# Spectra_Mirror_Bottom_Board_Final.net
KiCad netlist of a schematic drawn in EAGLE
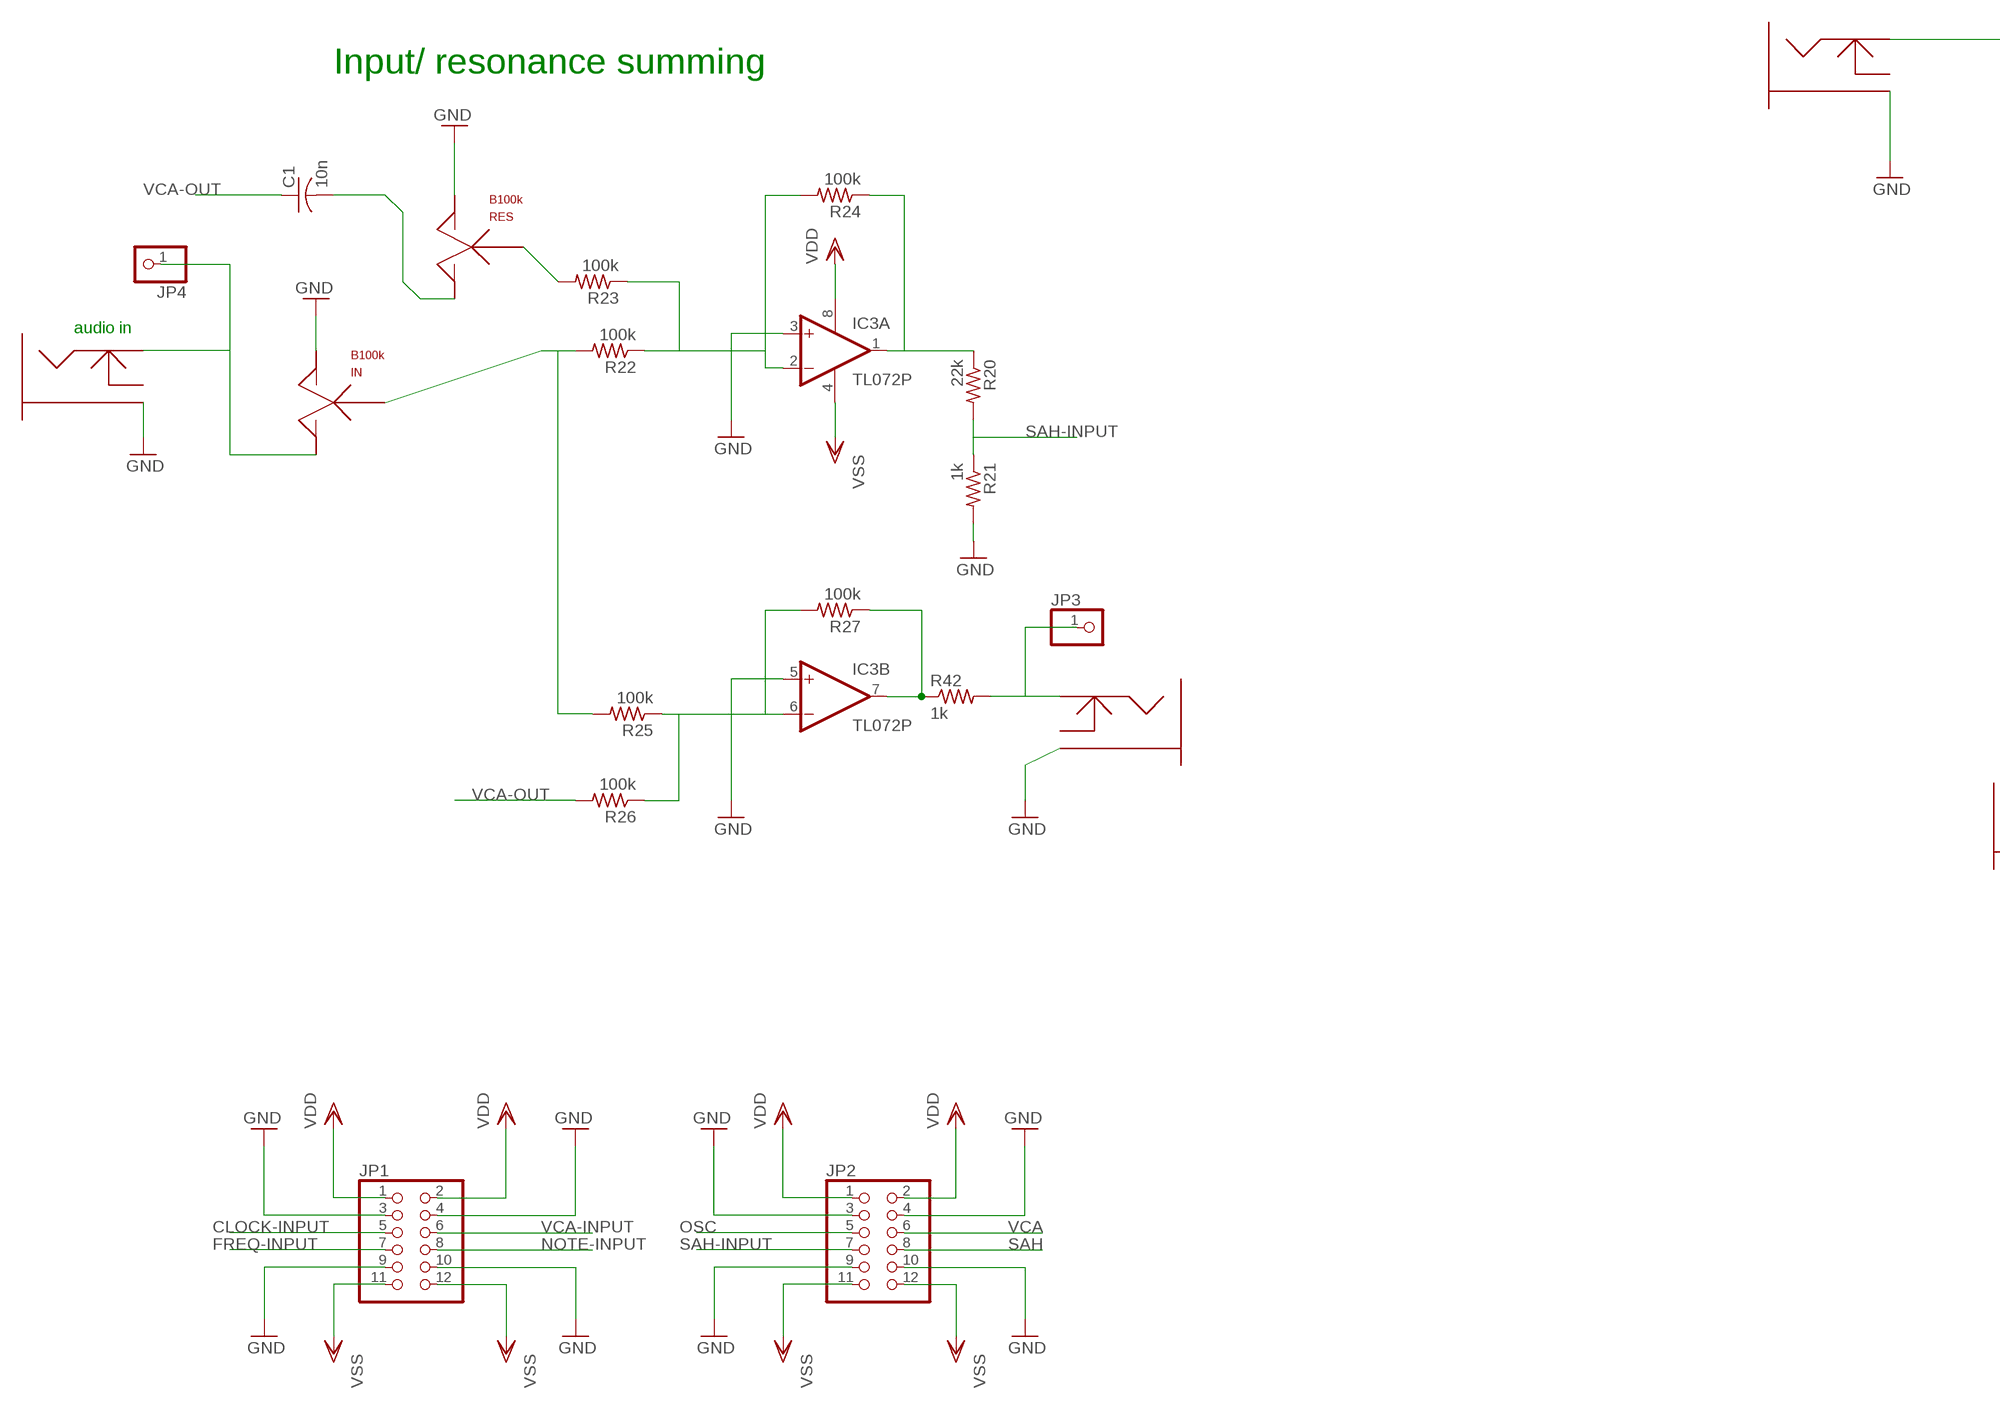
[diagram p0: schematic, sheet 1, part 1 of 2]
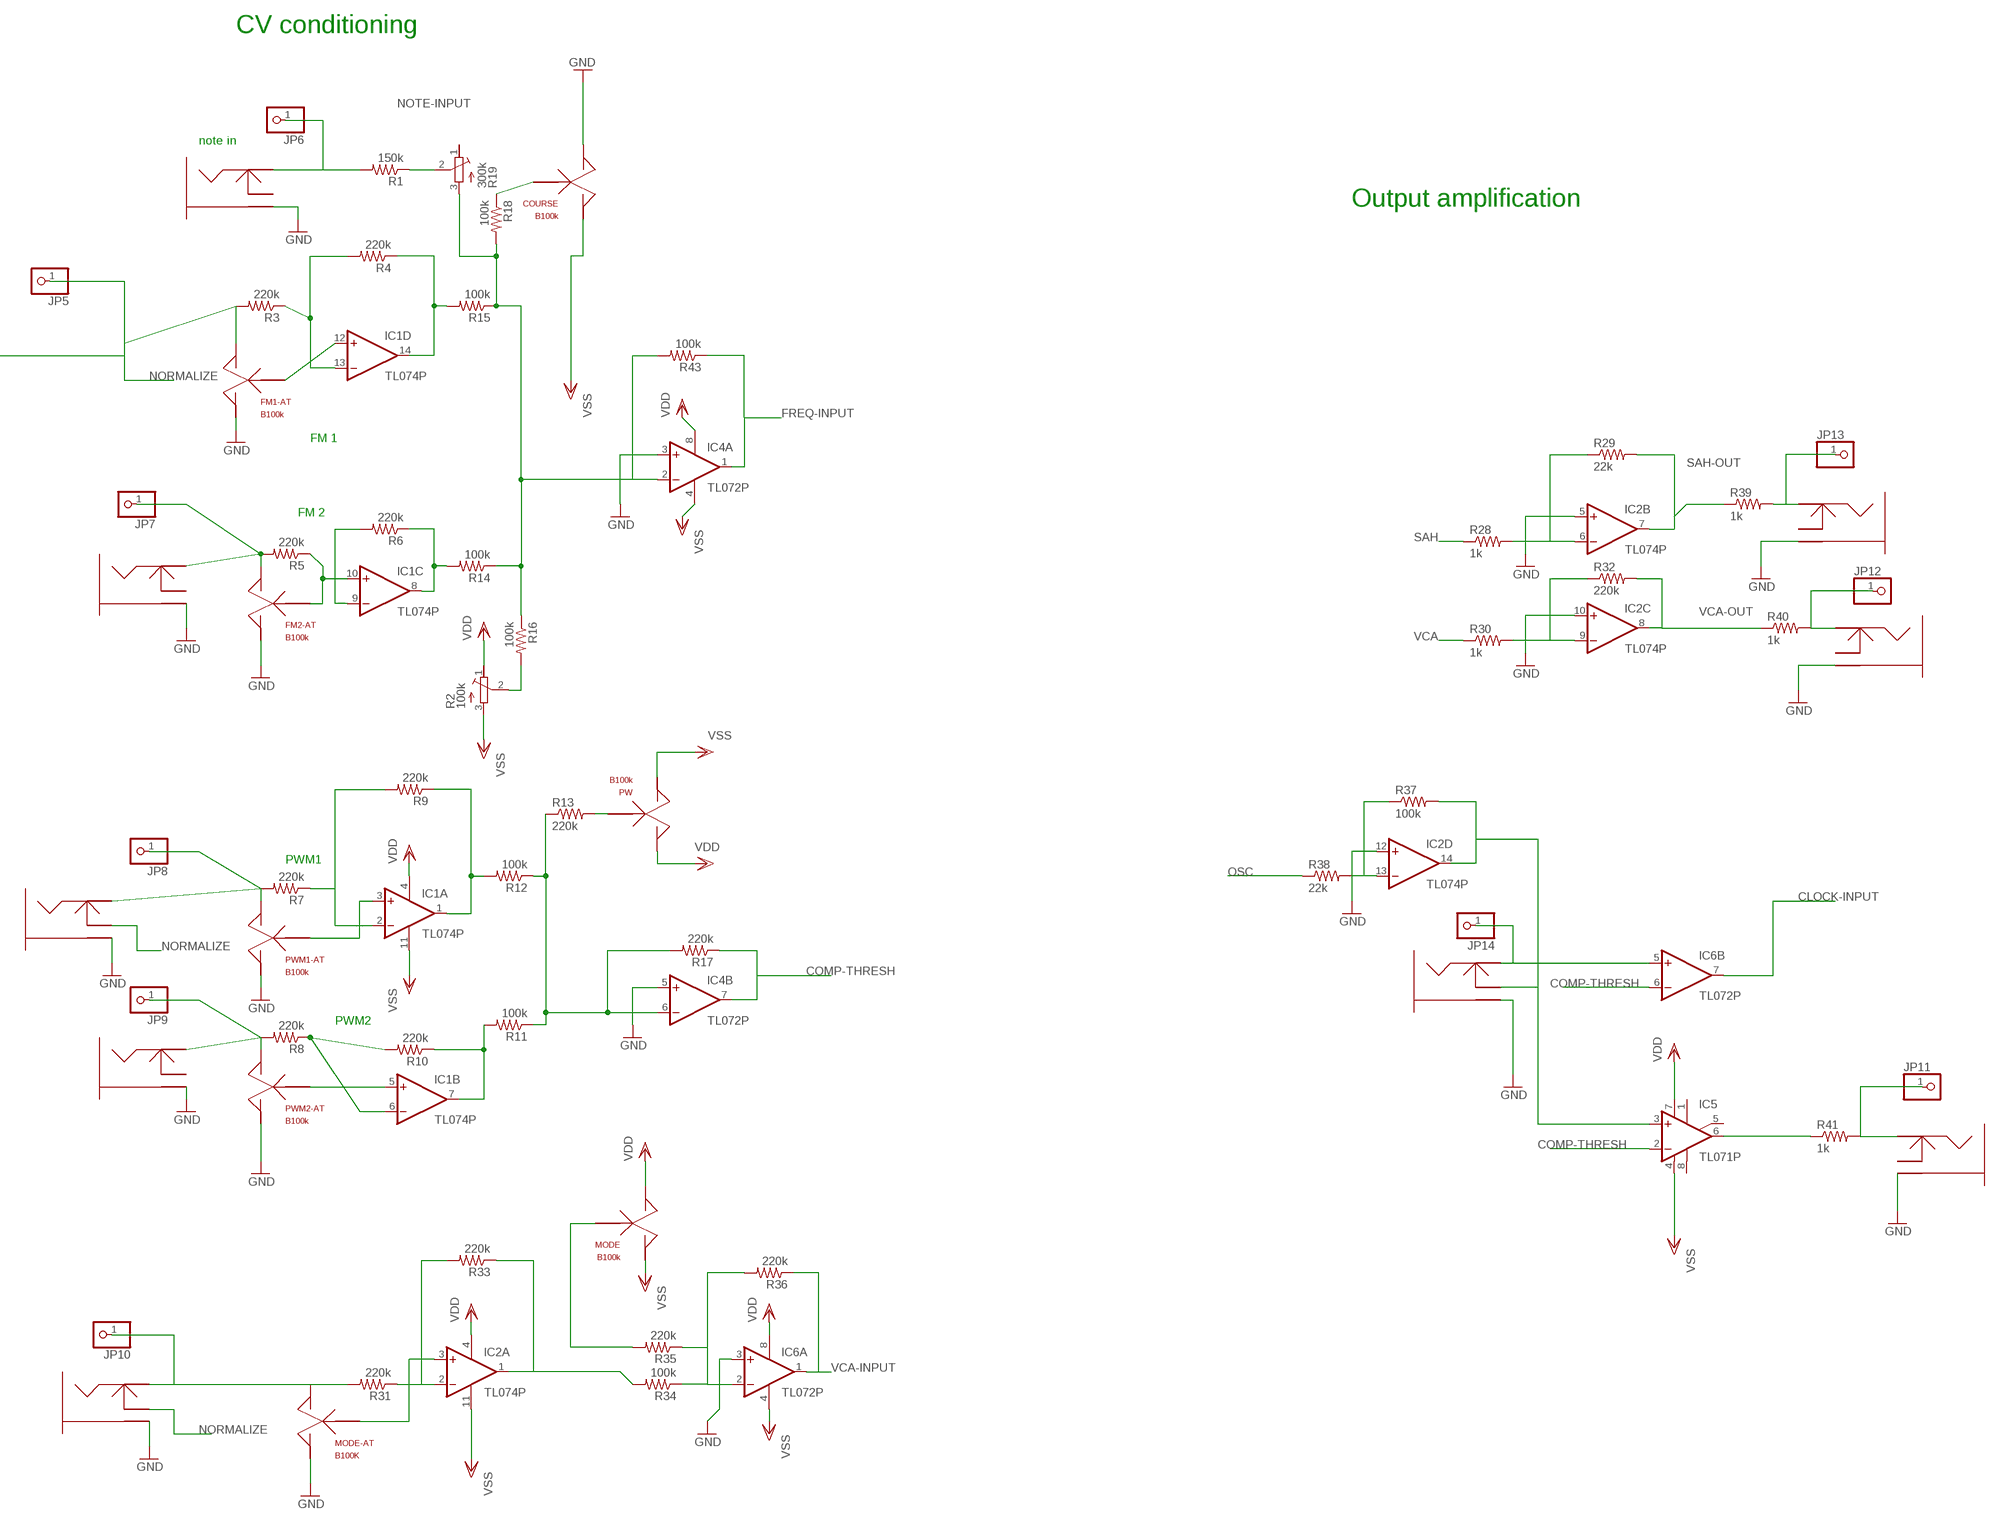
[diagram p1: schematic, sheet 1, part 2 of 2]

(export (version "E")
  (design (tool "Eeschema 10.0.6"))
  (components
    (comp (ref "C1")
      (value "10n")
      (footprint "eagle-import:C050-025X075")
      (libsource (lib "eagle-import") (part "C-US050-025X075"))
    )
    (comp (ref "COURSE")
      (value "B100k")
      (footprint "eagle-import:ALPHAPOT_BOARDMOUNT")
      (libsource (lib "eagle-import") (part "ALPHAPOT_BOARDMOUNT"))
    )
    (comp (ref "FM1-AT")
      (value "B100k")
      (footprint "eagle-import:ALPHAPOT_BOARDMOUNT")
      (libsource (lib "eagle-import") (part "ALPHAPOT_BOARDMOUNT"))
    )
    (comp (ref "FM2-AT")
      (value "B100k")
      (footprint "eagle-import:ALPHAPOT_BOARDMOUNT")
      (libsource (lib "eagle-import") (part "ALPHAPOT_BOARDMOUNT"))
    )
    (comp (ref "IC1")
      (value "TL074P")
      (footprint "eagle-import:DIL14")
      (libsource (lib "eagle-import") (part "TL074P"))
    )
    (comp (ref "IC2")
      (value "TL074P")
      (footprint "eagle-import:DIL14")
      (libsource (lib "eagle-import") (part "TL074P"))
    )
    (comp (ref "IC3")
      (value "TL072P")
      (footprint "eagle-import:DIL08")
      (libsource (lib "eagle-import") (part "TL072P"))
    )
    (comp (ref "IC4")
      (value "TL072P")
      (footprint "eagle-import:DIL08")
      (libsource (lib "eagle-import") (part "TL072P"))
    )
    (comp (ref "IC5")
      (value "TL071P")
      (footprint "eagle-import:DIL08")
      (libsource (lib "eagle-import") (part "TL071P"))
    )
    (comp (ref "IC6")
      (value "TL072P")
      (footprint "eagle-import:DIL08")
      (libsource (lib "eagle-import") (part "TL072P"))
    )
    (comp (ref "IN")
      (value "B100k")
      (footprint "eagle-import:ALPHAPOT_BOARDMOUNT")
      (libsource (lib "eagle-import") (part "ALPHAPOT_BOARDMOUNT"))
    )
    (comp (ref "JP1")
      (value "PINHD-2X6")
      (footprint "eagle-import:2X06")
      (libsource (lib "eagle-import") (part "PINHD-2X6"))
    )
    (comp (ref "JP2")
      (value "PINHD-2X6")
      (footprint "eagle-import:2X06")
      (libsource (lib "eagle-import") (part "PINHD-2X6"))
    )
    (comp (ref "JP3")
      (value "PINHD-1X1")
      (footprint "eagle-import:1X01")
      (libsource (lib "eagle-import") (part "PINHD-1X1"))
    )
    (comp (ref "JP4")
      (value "PINHD-1X1")
      (footprint "eagle-import:1X01")
      (libsource (lib "eagle-import") (part "PINHD-1X1"))
    )
    (comp (ref "JP5")
      (value "PINHD-1X1")
      (footprint "eagle-import:1X01")
      (libsource (lib "eagle-import") (part "PINHD-1X1"))
    )
    (comp (ref "JP6")
      (value "PINHD-1X1")
      (footprint "eagle-import:1X01")
      (libsource (lib "eagle-import") (part "PINHD-1X1"))
    )
    (comp (ref "JP7")
      (value "PINHD-1X1")
      (footprint "eagle-import:1X01")
      (libsource (lib "eagle-import") (part "PINHD-1X1"))
    )
    (comp (ref "JP8")
      (value "PINHD-1X1")
      (footprint "eagle-import:1X01")
      (libsource (lib "eagle-import") (part "PINHD-1X1"))
    )
    (comp (ref "JP9")
      (value "PINHD-1X1")
      (footprint "eagle-import:1X01")
      (libsource (lib "eagle-import") (part "PINHD-1X1"))
    )
    (comp (ref "JP10")
      (value "PINHD-1X1")
      (footprint "eagle-import:1X01")
      (libsource (lib "eagle-import") (part "PINHD-1X1"))
    )
    (comp (ref "JP11")
      (value "PINHD-1X1")
      (footprint "eagle-import:1X01")
      (libsource (lib "eagle-import") (part "PINHD-1X1"))
    )
    (comp (ref "JP12")
      (value "PINHD-1X1")
      (footprint "eagle-import:1X01")
      (libsource (lib "eagle-import") (part "PINHD-1X1"))
    )
    (comp (ref "JP13")
      (value "PINHD-1X1")
      (footprint "eagle-import:1X01")
      (libsource (lib "eagle-import") (part "PINHD-1X1"))
    )
    (comp (ref "JP14")
      (value "PINHD-1X1")
      (footprint "eagle-import:1X01")
      (libsource (lib "eagle-import") (part "PINHD-1X1"))
    )
    (comp (ref "MODE")
      (value "B100k")
      (footprint "eagle-import:ALPHAPOT_BOARDMOUNT")
      (libsource (lib "eagle-import") (part "ALPHAPOT_BOARDMOUNT"))
    )
    (comp (ref "MODE-AT")
      (value "B100K")
      (footprint "eagle-import:ALPHAPOT_BOARDMOUNT")
      (libsource (lib "eagle-import") (part "ALPHAPOT_BOARDMOUNT"))
    )
    (comp (ref "PW")
      (value "B100k")
      (footprint "eagle-import:ALPHAPOT_BOARDMOUNT")
      (libsource (lib "eagle-import") (part "ALPHAPOT_BOARDMOUNT"))
    )
    (comp (ref "PWM1-AT")
      (value "B100k")
      (footprint "eagle-import:ALPHAPOT_BOARDMOUNT")
      (libsource (lib "eagle-import") (part "ALPHAPOT_BOARDMOUNT"))
    )
    (comp (ref "PWM2-AT")
      (value "B100k")
      (footprint "eagle-import:ALPHAPOT_BOARDMOUNT")
      (libsource (lib "eagle-import") (part "ALPHAPOT_BOARDMOUNT"))
    )
    (comp (ref "R1")
      (value "150k")
      (footprint "eagle-import:0204_7")
      (libsource (lib "eagle-import") (part "R-US_0204/7"))
    )
    (comp (ref "R2")
      (value "100k")
      (footprint "eagle-import:RTRIMT93YA")
      (libsource (lib "eagle-import") (part "R-TRIMMT93YA"))
    )
    (comp (ref "R3")
      (value "220k")
      (footprint "eagle-import:0204_7")
      (libsource (lib "eagle-import") (part "R-US_0204/7"))
    )
    (comp (ref "R4")
      (value "220k")
      (footprint "eagle-import:0204V")
      (libsource (lib "eagle-import") (part "R-US_0204/2V"))
    )
    (comp (ref "R5")
      (value "220k")
      (footprint "eagle-import:0204_7")
      (libsource (lib "eagle-import") (part "R-US_0204/7"))
    )
    (comp (ref "R6")
      (value "220k")
      (footprint "eagle-import:0204V")
      (libsource (lib "eagle-import") (part "R-US_0204/2V"))
    )
    (comp (ref "R7")
      (value "220k")
      (footprint "eagle-import:0204_7")
      (libsource (lib "eagle-import") (part "R-US_0204/7"))
    )
    (comp (ref "R8")
      (value "220k")
      (footprint "eagle-import:0204_7")
      (libsource (lib "eagle-import") (part "R-US_0204/7"))
    )
    (comp (ref "R9")
      (value "220k")
      (footprint "eagle-import:0204V")
      (libsource (lib "eagle-import") (part "R-US_0204/2V"))
    )
    (comp (ref "R10")
      (value "220k")
      (footprint "eagle-import:0204_7")
      (libsource (lib "eagle-import") (part "R-US_0204/7"))
    )
    (comp (ref "R11")
      (value "100k")
      (footprint "eagle-import:0204_7")
      (libsource (lib "eagle-import") (part "R-US_0204/7"))
    )
    (comp (ref "R12")
      (value "100k")
      (footprint "eagle-import:0204_7")
      (libsource (lib "eagle-import") (part "R-US_0204/7"))
    )
    (comp (ref "R13")
      (value "220k")
      (footprint "eagle-import:0204_7")
      (libsource (lib "eagle-import") (part "R-US_0204/7"))
    )
    (comp (ref "R14")
      (value "100k")
      (footprint "eagle-import:0204_7")
      (libsource (lib "eagle-import") (part "R-US_0204/7"))
    )
    (comp (ref "R15")
      (value "100k")
      (footprint "eagle-import:0204_7")
      (libsource (lib "eagle-import") (part "R-US_0204/7"))
    )
    (comp (ref "R16")
      (value "100k")
      (footprint "eagle-import:0204_7")
      (libsource (lib "eagle-import") (part "R-US_0204/7"))
    )
    (comp (ref "R17")
      (value "220k")
      (footprint "eagle-import:0204_7")
      (libsource (lib "eagle-import") (part "R-US_0204/7"))
    )
    (comp (ref "R18")
      (value "100k")
      (footprint "eagle-import:0204_7")
      (libsource (lib "eagle-import") (part "R-US_0204/7"))
    )
    (comp (ref "R19")
      (value "300k")
      (footprint "eagle-import:RTRIMT93YA")
      (libsource (lib "eagle-import") (part "R-TRIMMT93YA"))
    )
    (comp (ref "R20")
      (value "22k")
      (footprint "eagle-import:0204_7")
      (libsource (lib "eagle-import") (part "R-US_0204/7"))
    )
    (comp (ref "R21")
      (value "1k")
      (footprint "eagle-import:0204_7")
      (libsource (lib "eagle-import") (part "R-US_0204/7"))
    )
    (comp (ref "R22")
      (value "100k")
      (footprint "eagle-import:0204_7")
      (libsource (lib "eagle-import") (part "R-US_0204/7"))
    )
    (comp (ref "R23")
      (value "100k")
      (footprint "eagle-import:0204_7")
      (libsource (lib "eagle-import") (part "R-US_0204/7"))
    )
    (comp (ref "R24")
      (value "100k")
      (footprint "eagle-import:0204_7")
      (libsource (lib "eagle-import") (part "R-US_0204/7"))
    )
    (comp (ref "R25")
      (value "100k")
      (footprint "eagle-import:0204_7")
      (libsource (lib "eagle-import") (part "R-US_0204/7"))
    )
    (comp (ref "R26")
      (value "100k")
      (footprint "eagle-import:0204_7")
      (libsource (lib "eagle-import") (part "R-US_0204/7"))
    )
    (comp (ref "R27")
      (value "100k")
      (footprint "eagle-import:0204_7")
      (libsource (lib "eagle-import") (part "R-US_0204/7"))
    )
    (comp (ref "R28")
      (value "1k")
      (footprint "eagle-import:0204_7")
      (libsource (lib "eagle-import") (part "R-US_0204/7"))
    )
    (comp (ref "R29")
      (value "22k")
      (footprint "eagle-import:0204V")
      (libsource (lib "eagle-import") (part "R-US_0204/2V"))
    )
    (comp (ref "R30")
      (value "1k")
      (footprint "eagle-import:0204_7")
      (libsource (lib "eagle-import") (part "R-US_0204/7"))
    )
    (comp (ref "R31")
      (value "220k")
      (footprint "eagle-import:0204_7")
      (libsource (lib "eagle-import") (part "R-US_0204/7"))
    )
    (comp (ref "R32")
      (value "220k")
      (footprint "eagle-import:0204_7")
      (libsource (lib "eagle-import") (part "R-US_0204/7"))
    )
    (comp (ref "R33")
      (value "220k")
      (footprint "eagle-import:0204V")
      (libsource (lib "eagle-import") (part "R-US_0204/2V"))
    )
    (comp (ref "R34")
      (value "100k")
      (footprint "eagle-import:0204_7")
      (libsource (lib "eagle-import") (part "R-US_0204/7"))
    )
    (comp (ref "R35")
      (value "220k")
      (footprint "eagle-import:0204_7")
      (libsource (lib "eagle-import") (part "R-US_0204/7"))
    )
    (comp (ref "R36")
      (value "220k")
      (footprint "eagle-import:0204_7")
      (libsource (lib "eagle-import") (part "R-US_0204/7"))
    )
    (comp (ref "R37")
      (value "100k")
      (footprint "eagle-import:0204V")
      (libsource (lib "eagle-import") (part "R-US_0204/2V"))
    )
    (comp (ref "R38")
      (value "22k")
      (footprint "eagle-import:0204_7")
      (libsource (lib "eagle-import") (part "R-US_0204/7"))
    )
    (comp (ref "R39")
      (value "1k")
      (footprint "eagle-import:0204_7")
      (libsource (lib "eagle-import") (part "R-US_0204/7"))
    )
    (comp (ref "R40")
      (value "1k")
      (footprint "eagle-import:0204_7")
      (libsource (lib "eagle-import") (part "R-US_0204/7"))
    )
    (comp (ref "R41")
      (value "1k")
      (footprint "eagle-import:0204_7")
      (libsource (lib "eagle-import") (part "R-US_0204/7"))
    )
    (comp (ref "R42")
      (value "1k")
      (footprint "eagle-import:0204_7")
      (libsource (lib "eagle-import") (part "R-US_0204/7"))
    )
    (comp (ref "R43")
      (value "100k")
      (footprint "eagle-import:0204_7")
      (libsource (lib "eagle-import") (part "R-US_0204/7"))
    )
    (comp (ref "RES")
      (value "B100k")
      (footprint "eagle-import:ALPHAPOT_BOARDMOUNT")
      (libsource (lib "eagle-import") (part "ALPHAPOT_BOARDMOUNT"))
    )
    (comp (ref "U$1")
      (value "KOBICONPJ-301")
      (footprint "eagle-import:KOBICONPJ-301")
      (libsource (lib "eagle-import") (part "KOBICONPJ-301"))
    )
    (comp (ref "U$2")
      (value "KOBICONPJ-301")
      (footprint "eagle-import:KOBICONPJ-301")
      (libsource (lib "eagle-import") (part "KOBICONPJ-301"))
    )
    (comp (ref "U$3")
      (value "KOBICONPJ-301")
      (footprint "eagle-import:KOBICONPJ-301")
      (libsource (lib "eagle-import") (part "KOBICONPJ-301"))
    )
    (comp (ref "U$4")
      (value "KOBICONPJ-301")
      (footprint "eagle-import:KOBICONPJ-301")
      (libsource (lib "eagle-import") (part "KOBICONPJ-301"))
    )
    (comp (ref "U$5")
      (value "KOBICONPJ-301")
      (footprint "eagle-import:KOBICONPJ-301")
      (libsource (lib "eagle-import") (part "KOBICONPJ-301"))
    )
    (comp (ref "U$6")
      (value "KOBICONPJ-301")
      (footprint "eagle-import:KOBICONPJ-301")
      (libsource (lib "eagle-import") (part "KOBICONPJ-301"))
    )
    (comp (ref "U$7")
      (value "KOBICONPJ-301")
      (footprint "eagle-import:KOBICONPJ-301")
      (libsource (lib "eagle-import") (part "KOBICONPJ-301"))
    )
    (comp (ref "U$8")
      (value "KOBICONPJ-301")
      (footprint "eagle-import:KOBICONPJ-301")
      (libsource (lib "eagle-import") (part "KOBICONPJ-301"))
    )
    (comp (ref "U$9")
      (value "KOBICONPJ-301")
      (footprint "eagle-import:KOBICONPJ-301")
      (libsource (lib "eagle-import") (part "KOBICONPJ-301"))
    )
    (comp (ref "U$10")
      (value "KOBICONPJ-301")
      (footprint "eagle-import:KOBICONPJ-301")
      (libsource (lib "eagle-import") (part "KOBICONPJ-301"))
    )
    (comp (ref "U$11")
      (value "KOBICONPJ-301")
      (footprint "eagle-import:KOBICONPJ-301")
      (libsource (lib "eagle-import") (part "KOBICONPJ-301"))
    )
    (comp (ref "U$12")
      (value "KOBICONPJ-301")
      (footprint "eagle-import:KOBICONPJ-301")
      (libsource (lib "eagle-import") (part "KOBICONPJ-301"))
    )
  )
  (nets
    (net (code "1") (name "/CLOCK-INPUT") (class "Default")
      (node (ref "IC6") (pin "7") (pinfunction "OUT_7") (pintype "output"))
      (node (ref "JP1") (pin "5") (pinfunction "5_5") (pintype "passive"))
    )
    (net (code "2") (name "/COMP-THRESH") (class "Default")
      (node (ref "IC4") (pin "7") (pinfunction "OUT_7") (pintype "output"))
      (node (ref "IC5") (pin "2") (pinfunction "-IN_2") (pintype "input"))
      (node (ref "IC6") (pin "6") (pinfunction "-IN_6") (pintype "input"))
      (node (ref "R17") (pin "1") (pinfunction "1_1") (pintype "passive"))
    )
    (net (code "3") (name "/FREQ-INPUT") (class "Default")
      (node (ref "IC4") (pin "1") (pinfunction "OUT_1") (pintype "output"))
      (node (ref "JP1") (pin "7") (pinfunction "7_7") (pintype "passive"))
      (node (ref "R43") (pin "1") (pinfunction "1_1") (pintype "passive"))
    )
    (net (code "4") (name "/NORMALIZE") (class "Default")
      (node (ref "FM1-AT") (pin "LEFT") (pinfunction "LEFT_LEFT") (pintype "bidirectional"))
      (node (ref "JP5") (pin "1") (pinfunction "1_1") (pintype "passive"))
      (node (ref "R3") (pin "2") (pinfunction "2_2") (pintype "passive"))
      (node (ref "U$10") (pin "SWITCH") (pinfunction "SWITCH_SWITCH") (pintype "bidirectional"))
      (node (ref "U$12") (pin "SWITCH") (pinfunction "SWITCH_SWITCH") (pintype "bidirectional"))
      (node (ref "U$3") (pin "IN") (pinfunction "INPUT_IN") (pintype "bidirectional"))
    )
    (net (code "5") (name "/NOTE-INPUT") (class "Default")
      (node (ref "JP1") (pin "8") (pinfunction "8_8") (pintype "passive"))
      (node (ref "JP6") (pin "1") (pinfunction "1_1") (pintype "passive"))
      (node (ref "R1") (pin "2") (pinfunction "2_2") (pintype "passive"))
      (node (ref "U$2") (pin "IN") (pinfunction "INPUT_IN") (pintype "bidirectional"))
    )
    (net (code "6") (name "/OSC") (class "Default")
      (node (ref "JP2") (pin "5") (pinfunction "5_5") (pintype "passive"))
      (node (ref "R38") (pin "1") (pinfunction "1_1") (pintype "passive"))
    )
    (net (code "7") (name "/SAH") (class "Default")
      (node (ref "JP2") (pin "8") (pinfunction "8_8") (pintype "passive"))
      (node (ref "R28") (pin "1") (pinfunction "1_1") (pintype "passive"))
    )
    (net (code "8") (name "/SAH-INPUT") (class "Default")
      (node (ref "JP2") (pin "7") (pinfunction "7_7") (pintype "passive"))
      (node (ref "R20") (pin "2") (pinfunction "2_2") (pintype "passive"))
      (node (ref "R21") (pin "1") (pinfunction "1_1") (pintype "passive"))
    )
    (net (code "9") (name "/SAH-OUT") (class "Default")
      (node (ref "IC2") (pin "7") (pinfunction "OUT_7") (pintype "output"))
      (node (ref "R29") (pin "2") (pinfunction "2_2") (pintype "passive"))
      (node (ref "R39") (pin "1") (pinfunction "1_1") (pintype "passive"))
    )
    (net (code "10") (name "/VCA") (class "Default")
      (node (ref "JP2") (pin "6") (pinfunction "6_6") (pintype "passive"))
      (node (ref "R30") (pin "1") (pinfunction "1_1") (pintype "passive"))
    )
    (net (code "11") (name "/VCA-INPUT") (class "Default")
      (node (ref "IC6") (pin "1") (pinfunction "OUT_1") (pintype "output"))
      (node (ref "JP1") (pin "6") (pinfunction "6_6") (pintype "passive"))
      (node (ref "R36") (pin "1") (pinfunction "1_1") (pintype "passive"))
    )
    (net (code "12") (name "/VCA-OUT") (class "Default")
      (node (ref "C1") (pin "1") (pinfunction "1_1") (pintype "passive"))
      (node (ref "IC2") (pin "8") (pinfunction "OUT_8") (pintype "output"))
      (node (ref "R26") (pin "2") (pinfunction "2_2") (pintype "passive"))
      (node (ref "R32") (pin "2") (pinfunction "2_2") (pintype "passive"))
      (node (ref "R40") (pin "1") (pinfunction "1_1") (pintype "passive"))
    )
    (net (code "13") (name "GND") (class "Default")
      (node (ref "COURSE") (pin "LEFT") (pinfunction "LEFT_LEFT") (pintype "bidirectional"))
      (node (ref "FM1-AT") (pin "RIGHT") (pinfunction "RIGHT_RIGHT") (pintype "bidirectional"))
      (node (ref "FM2-AT") (pin "RIGHT") (pinfunction "RIGHT_RIGHT") (pintype "bidirectional"))
      (node (ref "IC2") (pin "10") (pinfunction "+IN_10") (pintype "input"))
      (node (ref "IC2") (pin "12") (pinfunction "+IN_12") (pintype "input"))
      (node (ref "IC2") (pin "5") (pinfunction "+IN_5") (pintype "input"))
      (node (ref "IC3") (pin "3") (pinfunction "+IN_3") (pintype "input"))
      (node (ref "IC3") (pin "5") (pinfunction "+IN_5") (pintype "input"))
      (node (ref "IC4") (pin "3") (pinfunction "+IN_3") (pintype "input"))
      (node (ref "IC4") (pin "5") (pinfunction "+IN_5") (pintype "input"))
      (node (ref "IC6") (pin "3") (pinfunction "+IN_3") (pintype "input"))
      (node (ref "IN") (pin "RIGHT") (pinfunction "RIGHT_RIGHT") (pintype "bidirectional"))
      (node (ref "JP1") (pin "10") (pinfunction "10_10") (pintype "passive"))
      (node (ref "JP1") (pin "3") (pinfunction "3_3") (pintype "passive"))
      (node (ref "JP1") (pin "4") (pinfunction "4_4") (pintype "passive"))
      (node (ref "JP1") (pin "9") (pinfunction "9_9") (pintype "passive"))
      (node (ref "JP2") (pin "10") (pinfunction "10_10") (pintype "passive"))
      (node (ref "JP2") (pin "3") (pinfunction "3_3") (pintype "passive"))
      (node (ref "JP2") (pin "4") (pinfunction "4_4") (pintype "passive"))
      (node (ref "JP2") (pin "9") (pinfunction "9_9") (pintype "passive"))
      (node (ref "MODE-AT") (pin "RIGHT") (pinfunction "RIGHT_RIGHT") (pintype "bidirectional"))
      (node (ref "PWM1-AT") (pin "RIGHT") (pinfunction "RIGHT_RIGHT") (pintype "bidirectional"))
      (node (ref "PWM2-AT") (pin "RIGHT") (pinfunction "RIGHT_RIGHT") (pintype "bidirectional"))
      (node (ref "R21") (pin "2") (pinfunction "2_2") (pintype "passive"))
      (node (ref "RES") (pin "RIGHT") (pinfunction "RIGHT_RIGHT") (pintype "bidirectional"))
      (node (ref "U$1") (pin "GND") (pinfunction "GROUND_GND") (pintype "bidirectional"))
      (node (ref "U$1") (pin "GND2") (pinfunction "GROUND_GND2") (pintype "bidirectional"))
      (node (ref "U$10") (pin "GND") (pinfunction "GROUND_GND") (pintype "bidirectional"))
      (node (ref "U$10") (pin "GND2") (pinfunction "GROUND_GND2") (pintype "bidirectional"))
      (node (ref "U$11") (pin "GND") (pinfunction "GROUND_GND") (pintype "bidirectional"))
      (node (ref "U$11") (pin "GND2") (pinfunction "GROUND_GND2") (pintype "bidirectional"))
      (node (ref "U$12") (pin "GND") (pinfunction "GROUND_GND") (pintype "bidirectional"))
      (node (ref "U$12") (pin "GND2") (pinfunction "GROUND_GND2") (pintype "bidirectional"))
      (node (ref "U$2") (pin "GND") (pinfunction "GROUND_GND") (pintype "bidirectional"))
      (node (ref "U$2") (pin "GND2") (pinfunction "GROUND_GND2") (pintype "bidirectional"))
      (node (ref "U$3") (pin "GND") (pinfunction "GROUND_GND") (pintype "bidirectional"))
      (node (ref "U$3") (pin "GND2") (pinfunction "GROUND_GND2") (pintype "bidirectional"))
      (node (ref "U$4") (pin "GND") (pinfunction "GROUND_GND") (pintype "bidirectional"))
      (node (ref "U$4") (pin "GND2") (pinfunction "GROUND_GND2") (pintype "bidirectional"))
      (node (ref "U$5") (pin "GND") (pinfunction "GROUND_GND") (pintype "bidirectional"))
      (node (ref "U$5") (pin "GND2") (pinfunction "GROUND_GND2") (pintype "bidirectional"))
      (node (ref "U$6") (pin "GND") (pinfunction "GROUND_GND") (pintype "bidirectional"))
      (node (ref "U$6") (pin "GND2") (pinfunction "GROUND_GND2") (pintype "bidirectional"))
      (node (ref "U$7") (pin "GND") (pinfunction "GROUND_GND") (pintype "bidirectional"))
      (node (ref "U$7") (pin "GND2") (pinfunction "GROUND_GND2") (pintype "bidirectional"))
      (node (ref "U$8") (pin "GND") (pinfunction "GROUND_GND") (pintype "bidirectional"))
      (node (ref "U$8") (pin "GND2") (pinfunction "GROUND_GND2") (pintype "bidirectional"))
      (node (ref "U$9") (pin "GND") (pinfunction "GROUND_GND") (pintype "bidirectional"))
      (node (ref "U$9") (pin "GND2") (pinfunction "GROUND_GND2") (pintype "bidirectional"))
    )
    (net (code "14") (name "Net-(C1-Pad2)") (class "Default")
      (node (ref "C1") (pin "2") (pinfunction "2_2") (pintype "passive"))
      (node (ref "RES") (pin "LEFT") (pinfunction "LEFT_LEFT") (pintype "bidirectional"))
    )
    (net (code "15") (name "Net-(COURSE-PadMID)") (class "Default")
      (node (ref "COURSE") (pin "MID") (pinfunction "MID_MID") (pintype "bidirectional"))
      (node (ref "R18") (pin "1") (pinfunction "1_1") (pintype "passive"))
    )
    (net (code "16") (name "Net-(IC1A-+IN)") (class "Default")
      (node (ref "IC1") (pin "3") (pinfunction "+IN_3") (pintype "input"))
      (node (ref "PWM1-AT") (pin "MID") (pinfunction "MID_MID") (pintype "bidirectional"))
    )
    (net (code "17") (name "Net-(IC1A--IN)") (class "Default")
      (node (ref "IC1") (pin "2") (pinfunction "-IN_2") (pintype "input"))
      (node (ref "R7") (pin "1") (pinfunction "1_1") (pintype "passive"))
      (node (ref "R9") (pin "2") (pinfunction "2_2") (pintype "passive"))
    )
    (net (code "18") (name "Net-(IC1A-OUT)") (class "Default")
      (node (ref "IC1") (pin "1") (pinfunction "OUT_1") (pintype "output"))
      (node (ref "R12") (pin "2") (pinfunction "2_2") (pintype "passive"))
      (node (ref "R9") (pin "1") (pinfunction "1_1") (pintype "passive"))
    )
    (net (code "19") (name "Net-(IC1B-+IN)") (class "Default")
      (node (ref "IC1") (pin "5") (pinfunction "+IN_5") (pintype "input"))
      (node (ref "PWM2-AT") (pin "MID") (pinfunction "MID_MID") (pintype "bidirectional"))
    )
    (net (code "20") (name "Net-(IC1B--IN)") (class "Default")
      (node (ref "IC1") (pin "6") (pinfunction "-IN_6") (pintype "input"))
      (node (ref "R10") (pin "2") (pinfunction "2_2") (pintype "passive"))
      (node (ref "R8") (pin "1") (pinfunction "1_1") (pintype "passive"))
    )
    (net (code "21") (name "Net-(IC1B-OUT)") (class "Default")
      (node (ref "IC1") (pin "7") (pinfunction "OUT_7") (pintype "output"))
      (node (ref "R10") (pin "1") (pinfunction "1_1") (pintype "passive"))
      (node (ref "R11") (pin "2") (pinfunction "2_2") (pintype "passive"))
    )
    (net (code "22") (name "Net-(IC1C-+IN)") (class "Default")
      (node (ref "FM2-AT") (pin "MID") (pinfunction "MID_MID") (pintype "bidirectional"))
      (node (ref "IC1") (pin "10") (pinfunction "+IN_10") (pintype "input"))
      (node (ref "R5") (pin "1") (pinfunction "1_1") (pintype "passive"))
    )
    (net (code "23") (name "Net-(IC1C--IN)") (class "Default")
      (node (ref "IC1") (pin "9") (pinfunction "-IN_9") (pintype "input"))
      (node (ref "R6") (pin "2") (pinfunction "2_2") (pintype "passive"))
    )
    (net (code "24") (name "Net-(IC1C-OUT)") (class "Default")
      (node (ref "IC1") (pin "8") (pinfunction "OUT_8") (pintype "output"))
      (node (ref "R14") (pin "2") (pinfunction "2_2") (pintype "passive"))
      (node (ref "R6") (pin "1") (pinfunction "1_1") (pintype "passive"))
    )
    (net (code "25") (name "Net-(IC1D-+IN)") (class "Default")
      (node (ref "FM1-AT") (pin "MID") (pinfunction "MID_MID") (pintype "bidirectional"))
      (node (ref "IC1") (pin "12") (pinfunction "+IN_12") (pintype "input"))
    )
    (net (code "26") (name "Net-(IC1D--IN)") (class "Default")
      (node (ref "IC1") (pin "13") (pinfunction "-IN_13") (pintype "input"))
      (node (ref "R3") (pin "1") (pinfunction "1_1") (pintype "passive"))
      (node (ref "R4") (pin "2") (pinfunction "2_2") (pintype "passive"))
    )
    (net (code "27") (name "Net-(IC1D-OUT)") (class "Default")
      (node (ref "IC1") (pin "14") (pinfunction "OUT_14") (pintype "output"))
      (node (ref "R15") (pin "2") (pinfunction "2_2") (pintype "passive"))
      (node (ref "R4") (pin "1") (pinfunction "1_1") (pintype "passive"))
    )
    (net (code "28") (name "Net-(IC2A-+IN)") (class "Default")
      (node (ref "IC2") (pin "3") (pinfunction "+IN_3") (pintype "input"))
      (node (ref "MODE-AT") (pin "MID") (pinfunction "MID_MID") (pintype "bidirectional"))
    )
    (net (code "29") (name "Net-(IC2A--IN)") (class "Default")
      (node (ref "IC2") (pin "2") (pinfunction "-IN_2") (pintype "input"))
      (node (ref "R31") (pin "1") (pinfunction "1_1") (pintype "passive"))
      (node (ref "R33") (pin "2") (pinfunction "2_2") (pintype "passive"))
    )
    (net (code "30") (name "Net-(IC2A-OUT)") (class "Default")
      (node (ref "IC2") (pin "1") (pinfunction "OUT_1") (pintype "output"))
      (node (ref "R33") (pin "1") (pinfunction "1_1") (pintype "passive"))
      (node (ref "R34") (pin "2") (pinfunction "2_2") (pintype "passive"))
    )
    (net (code "31") (name "Net-(IC2B--IN)") (class "Default")
      (node (ref "IC2") (pin "6") (pinfunction "-IN_6") (pintype "input"))
      (node (ref "R28") (pin "2") (pinfunction "2_2") (pintype "passive"))
      (node (ref "R29") (pin "1") (pinfunction "1_1") (pintype "passive"))
    )
    (net (code "32") (name "Net-(IC2C--IN)") (class "Default")
      (node (ref "IC2") (pin "9") (pinfunction "-IN_9") (pintype "input"))
      (node (ref "R30") (pin "2") (pinfunction "2_2") (pintype "passive"))
      (node (ref "R32") (pin "1") (pinfunction "1_1") (pintype "passive"))
    )
    (net (code "33") (name "Net-(IC2D--IN)") (class "Default")
      (node (ref "IC2") (pin "13") (pinfunction "-IN_13") (pintype "input"))
      (node (ref "R37") (pin "1") (pinfunction "1_1") (pintype "passive"))
      (node (ref "R38") (pin "2") (pinfunction "2_2") (pintype "passive"))
    )
    (net (code "34") (name "Net-(IC2D-OUT)") (class "Default")
      (node (ref "IC2") (pin "14") (pinfunction "OUT_14") (pintype "output"))
      (node (ref "IC5") (pin "3") (pinfunction "+IN_3") (pintype "input"))
      (node (ref "R37") (pin "2") (pinfunction "2_2") (pintype "passive"))
      (node (ref "U$9") (pin "SWITCH") (pinfunction "SWITCH_SWITCH") (pintype "bidirectional"))
    )
    (net (code "35") (name "Net-(IC3A--IN)") (class "Default")
      (node (ref "IC3") (pin "2") (pinfunction "-IN_2") (pintype "input"))
      (node (ref "R22") (pin "1") (pinfunction "1_1") (pintype "passive"))
      (node (ref "R23") (pin "1") (pinfunction "1_1") (pintype "passive"))
      (node (ref "R24") (pin "2") (pinfunction "2_2") (pintype "passive"))
    )
    (net (code "36") (name "Net-(IC3A-OUT)") (class "Default")
      (node (ref "IC3") (pin "1") (pinfunction "OUT_1") (pintype "output"))
      (node (ref "R20") (pin "1") (pinfunction "1_1") (pintype "passive"))
      (node (ref "R24") (pin "1") (pinfunction "1_1") (pintype "passive"))
    )
    (net (code "37") (name "Net-(IC3B--IN)") (class "Default")
      (node (ref "IC3") (pin "6") (pinfunction "-IN_6") (pintype "input"))
      (node (ref "R25") (pin "1") (pinfunction "1_1") (pintype "passive"))
      (node (ref "R26") (pin "1") (pinfunction "1_1") (pintype "passive"))
      (node (ref "R27") (pin "2") (pinfunction "2_2") (pintype "passive"))
    )
    (net (code "38") (name "Net-(IC3B-OUT)") (class "Default")
      (node (ref "IC3") (pin "7") (pinfunction "OUT_7") (pintype "output"))
      (node (ref "R27") (pin "1") (pinfunction "1_1") (pintype "passive"))
      (node (ref "R42") (pin "1") (pinfunction "1_1") (pintype "passive"))
    )
    (net (code "39") (name "Net-(IC4A--IN)") (class "Default")
      (node (ref "IC4") (pin "2") (pinfunction "-IN_2") (pintype "input"))
      (node (ref "R14") (pin "1") (pinfunction "1_1") (pintype "passive"))
      (node (ref "R15") (pin "1") (pinfunction "1_1") (pintype "passive"))
      (node (ref "R16") (pin "1") (pinfunction "1_1") (pintype "passive"))
      (node (ref "R18") (pin "2") (pinfunction "2_2") (pintype "passive"))
      (node (ref "R19") (pin "3") (pinfunction "A_3") (pintype "passive"))
      (node (ref "R43") (pin "2") (pinfunction "2_2") (pintype "passive"))
    )
    (net (code "40") (name "Net-(IC4B--IN)") (class "Default")
      (node (ref "IC4") (pin "6") (pinfunction "-IN_6") (pintype "input"))
      (node (ref "R11") (pin "1") (pinfunction "1_1") (pintype "passive"))
      (node (ref "R12") (pin "1") (pinfunction "1_1") (pintype "passive"))
      (node (ref "R13") (pin "1") (pinfunction "1_1") (pintype "passive"))
      (node (ref "R17") (pin "2") (pinfunction "2_2") (pintype "passive"))
    )
    (net (code "41") (name "Net-(IC5-OUT)") (class "Default")
      (node (ref "IC5") (pin "6") (pinfunction "OUT_6") (pintype "output"))
      (node (ref "R41") (pin "1") (pinfunction "1_1") (pintype "passive"))
    )
    (net (code "42") (name "Net-(IC6A--IN)") (class "Default")
      (node (ref "IC6") (pin "2") (pinfunction "-IN_2") (pintype "input"))
      (node (ref "R34") (pin "1") (pinfunction "1_1") (pintype "passive"))
      (node (ref "R35") (pin "1") (pinfunction "1_1") (pintype "passive"))
      (node (ref "R36") (pin "2") (pinfunction "2_2") (pintype "passive"))
    )
    (net (code "43") (name "Net-(IC6B-+IN)") (class "Default")
      (node (ref "IC6") (pin "5") (pinfunction "+IN_5") (pintype "input"))
      (node (ref "JP14") (pin "1") (pinfunction "1_1") (pintype "passive"))
      (node (ref "U$9") (pin "IN") (pinfunction "INPUT_IN") (pintype "bidirectional"))
    )
    (net (code "44") (name "Net-(IN-PadMID)") (class "Default")
      (node (ref "IN") (pin "MID") (pinfunction "MID_MID") (pintype "bidirectional"))
      (node (ref "R22") (pin "2") (pinfunction "2_2") (pintype "passive"))
      (node (ref "R25") (pin "2") (pinfunction "2_2") (pintype "passive"))
    )
    (net (code "45") (name "Net-(MODE-PadMID)") (class "Default")
      (node (ref "MODE") (pin "MID") (pinfunction "MID_MID") (pintype "bidirectional"))
      (node (ref "R35") (pin "2") (pinfunction "2_2") (pintype "passive"))
    )
    (net (code "46") (name "Net-(PW-PadMID)") (class "Default")
      (node (ref "PW") (pin "MID") (pinfunction "MID_MID") (pintype "bidirectional"))
      (node (ref "R13") (pin "2") (pinfunction "2_2") (pintype "passive"))
    )
    (net (code "47") (name "Net-(R2-S)") (class "Default")
      (node (ref "R16") (pin "2") (pinfunction "2_2") (pintype "passive"))
      (node (ref "R2") (pin "2") (pinfunction "S_2") (pintype "passive"))
    )
    (net (code "48") (name "Net-(R19-S)") (class "Default")
      (node (ref "R1") (pin "1") (pinfunction "1_1") (pintype "passive"))
      (node (ref "R19") (pin "2") (pinfunction "S_2") (pintype "passive"))
    )
    (net (code "49") (name "Net-(R23-Pad2)") (class "Default")
      (node (ref "R23") (pin "2") (pinfunction "2_2") (pintype "passive"))
      (node (ref "RES") (pin "MID") (pinfunction "MID_MID") (pintype "bidirectional"))
    )
    (net (code "50") (name "Net-(U$1-INPUT)") (class "Default")
      (node (ref "IN") (pin "LEFT") (pinfunction "LEFT_LEFT") (pintype "bidirectional"))
      (node (ref "JP4") (pin "1") (pinfunction "1_1") (pintype "passive"))
      (node (ref "U$1") (pin "IN") (pinfunction "INPUT_IN") (pintype "bidirectional"))
    )
    (net (code "51") (name "Net-(U$4-INPUT)") (class "Default")
      (node (ref "FM2-AT") (pin "LEFT") (pinfunction "LEFT_LEFT") (pintype "bidirectional"))
      (node (ref "JP7") (pin "1") (pinfunction "1_1") (pintype "passive"))
      (node (ref "R5") (pin "2") (pinfunction "2_2") (pintype "passive"))
      (node (ref "U$4") (pin "IN") (pinfunction "INPUT_IN") (pintype "bidirectional"))
    )
    (net (code "52") (name "Net-(U$5-INPUT)") (class "Default")
      (node (ref "JP11") (pin "1") (pinfunction "1_1") (pintype "passive"))
      (node (ref "R41") (pin "2") (pinfunction "2_2") (pintype "passive"))
      (node (ref "U$5") (pin "IN") (pinfunction "INPUT_IN") (pintype "bidirectional"))
    )
    (net (code "53") (name "Net-(U$6-INPUT)") (class "Default")
      (node (ref "JP13") (pin "1") (pinfunction "1_1") (pintype "passive"))
      (node (ref "R39") (pin "2") (pinfunction "2_2") (pintype "passive"))
      (node (ref "U$6") (pin "IN") (pinfunction "INPUT_IN") (pintype "bidirectional"))
    )
    (net (code "54") (name "Net-(U$7-INPUT)") (class "Default")
      (node (ref "JP12") (pin "1") (pinfunction "1_1") (pintype "passive"))
      (node (ref "R40") (pin "2") (pinfunction "2_2") (pintype "passive"))
      (node (ref "U$7") (pin "IN") (pinfunction "INPUT_IN") (pintype "bidirectional"))
    )
    (net (code "55") (name "Net-(U$8-INPUT)") (class "Default")
      (node (ref "JP3") (pin "1") (pinfunction "1_1") (pintype "passive"))
      (node (ref "R42") (pin "2") (pinfunction "2_2") (pintype "passive"))
      (node (ref "U$8") (pin "IN") (pinfunction "INPUT_IN") (pintype "bidirectional"))
    )
    (net (code "56") (name "Net-(U$10-INPUT)") (class "Default")
      (node (ref "JP10") (pin "1") (pinfunction "1_1") (pintype "passive"))
      (node (ref "MODE-AT") (pin "LEFT") (pinfunction "LEFT_LEFT") (pintype "bidirectional"))
      (node (ref "R31") (pin "2") (pinfunction "2_2") (pintype "passive"))
      (node (ref "U$10") (pin "IN") (pinfunction "INPUT_IN") (pintype "bidirectional"))
    )
    (net (code "57") (name "Net-(U$11-INPUT)") (class "Default")
      (node (ref "JP9") (pin "1") (pinfunction "1_1") (pintype "passive"))
      (node (ref "PWM2-AT") (pin "LEFT") (pinfunction "LEFT_LEFT") (pintype "bidirectional"))
      (node (ref "R8") (pin "2") (pinfunction "2_2") (pintype "passive"))
      (node (ref "U$11") (pin "IN") (pinfunction "INPUT_IN") (pintype "bidirectional"))
    )
    (net (code "58") (name "Net-(U$12-INPUT)") (class "Default")
      (node (ref "JP8") (pin "1") (pinfunction "1_1") (pintype "passive"))
      (node (ref "PWM1-AT") (pin "LEFT") (pinfunction "LEFT_LEFT") (pintype "bidirectional"))
      (node (ref "R7") (pin "2") (pinfunction "2_2") (pintype "passive"))
      (node (ref "U$12") (pin "IN") (pinfunction "INPUT_IN") (pintype "bidirectional"))
    )
    (net (code "59") (name "VDD") (class "Default")
      (node (ref "IC1") (pin "4") (pinfunction "V+_4") (pintype "power_in"))
      (node (ref "IC2") (pin "4") (pinfunction "V+_4") (pintype "power_in"))
      (node (ref "IC3") (pin "8") (pinfunction "V+_8") (pintype "power_in"))
      (node (ref "IC4") (pin "8") (pinfunction "V+_8") (pintype "power_in"))
      (node (ref "IC5") (pin "7") (pinfunction "V+_7") (pintype "power_in"))
      (node (ref "IC6") (pin "8") (pinfunction "V+_8") (pintype "power_in"))
      (node (ref "JP1") (pin "1") (pinfunction "1_1") (pintype "passive"))
      (node (ref "JP1") (pin "2") (pinfunction "2_2") (pintype "passive"))
      (node (ref "JP2") (pin "1") (pinfunction "1_1") (pintype "passive"))
      (node (ref "JP2") (pin "2") (pinfunction "2_2") (pintype "passive"))
      (node (ref "MODE") (pin "LEFT") (pinfunction "LEFT_LEFT") (pintype "bidirectional"))
      (node (ref "PW") (pin "LEFT") (pinfunction "LEFT_LEFT") (pintype "bidirectional"))
      (node (ref "R2") (pin "1") (pinfunction "E_1") (pintype "passive"))
    )
    (net (code "60") (name "VSS") (class "Default")
      (node (ref "COURSE") (pin "RIGHT") (pinfunction "RIGHT_RIGHT") (pintype "bidirectional"))
      (node (ref "IC1") (pin "11") (pinfunction "V-_11") (pintype "power_in"))
      (node (ref "IC2") (pin "11") (pinfunction "V-_11") (pintype "power_in"))
      (node (ref "IC3") (pin "4") (pinfunction "V-_4") (pintype "power_in"))
      (node (ref "IC4") (pin "4") (pinfunction "V-_4") (pintype "power_in"))
      (node (ref "IC5") (pin "4") (pinfunction "V-_4") (pintype "power_in"))
      (node (ref "IC6") (pin "4") (pinfunction "V-_4") (pintype "power_in"))
      (node (ref "JP1") (pin "11") (pinfunction "11_11") (pintype "passive"))
      (node (ref "JP1") (pin "12") (pinfunction "12_12") (pintype "passive"))
      (node (ref "JP2") (pin "11") (pinfunction "11_11") (pintype "passive"))
      (node (ref "JP2") (pin "12") (pinfunction "12_12") (pintype "passive"))
      (node (ref "MODE") (pin "RIGHT") (pinfunction "RIGHT_RIGHT") (pintype "bidirectional"))
      (node (ref "PW") (pin "RIGHT") (pinfunction "RIGHT_RIGHT") (pintype "bidirectional"))
      (node (ref "R2") (pin "3") (pinfunction "A_3") (pintype "passive"))
    )
    (net (code "61") (name "unconnected-(IC5-ON1-Pad1)") (class "Default")
      (node (ref "IC5") (pin "1") (pinfunction "ON1_1") (pintype "passive"))
    )
    (net (code "62") (name "unconnected-(IC5-ON2-Pad5)") (class "Default")
      (node (ref "IC5") (pin "5") (pinfunction "ON2_5") (pintype "passive"))
    )
    (net (code "63") (name "unconnected-(IC5-OPT-Pad8)") (class "Default")
      (node (ref "IC5") (pin "8") (pinfunction "OPT_8") (pintype "passive"))
    )
    (net (code "64") (name "unconnected-(R19-E-Pad1)") (class "Default")
      (node (ref "R19") (pin "1") (pinfunction "E_1") (pintype "passive"))
    )
    (net (code "65") (name "unconnected-(U$1-PadSWITCH)") (class "Default")
      (node (ref "U$1") (pin "SWITCH") (pinfunction "SWITCH_SWITCH") (pintype "bidirectional"))
    )
    (net (code "66") (name "unconnected-(U$2-PadSWITCH)") (class "Default")
      (node (ref "U$2") (pin "SWITCH") (pinfunction "SWITCH_SWITCH") (pintype "bidirectional"))
    )
    (net (code "67") (name "unconnected-(U$3-PadSWITCH)") (class "Default")
      (node (ref "U$3") (pin "SWITCH") (pinfunction "SWITCH_SWITCH") (pintype "bidirectional"))
    )
    (net (code "68") (name "unconnected-(U$4-PadSWITCH)") (class "Default")
      (node (ref "U$4") (pin "SWITCH") (pinfunction "SWITCH_SWITCH") (pintype "bidirectional"))
    )
    (net (code "69") (name "unconnected-(U$5-PadSWITCH)") (class "Default")
      (node (ref "U$5") (pin "SWITCH") (pinfunction "SWITCH_SWITCH") (pintype "bidirectional"))
    )
    (net (code "70") (name "unconnected-(U$6-PadSWITCH)") (class "Default")
      (node (ref "U$6") (pin "SWITCH") (pinfunction "SWITCH_SWITCH") (pintype "bidirectional"))
    )
    (net (code "71") (name "unconnected-(U$7-PadSWITCH)") (class "Default")
      (node (ref "U$7") (pin "SWITCH") (pinfunction "SWITCH_SWITCH") (pintype "bidirectional"))
    )
    (net (code "72") (name "unconnected-(U$8-PadSWITCH)") (class "Default")
      (node (ref "U$8") (pin "SWITCH") (pinfunction "SWITCH_SWITCH") (pintype "bidirectional"))
    )
    (net (code "73") (name "unconnected-(U$11-PadSWITCH)") (class "Default")
      (node (ref "U$11") (pin "SWITCH") (pinfunction "SWITCH_SWITCH") (pintype "bidirectional"))
    )
  )
)
